# M129X.net
KiCad netlist of a schematic drawn in EAGLE
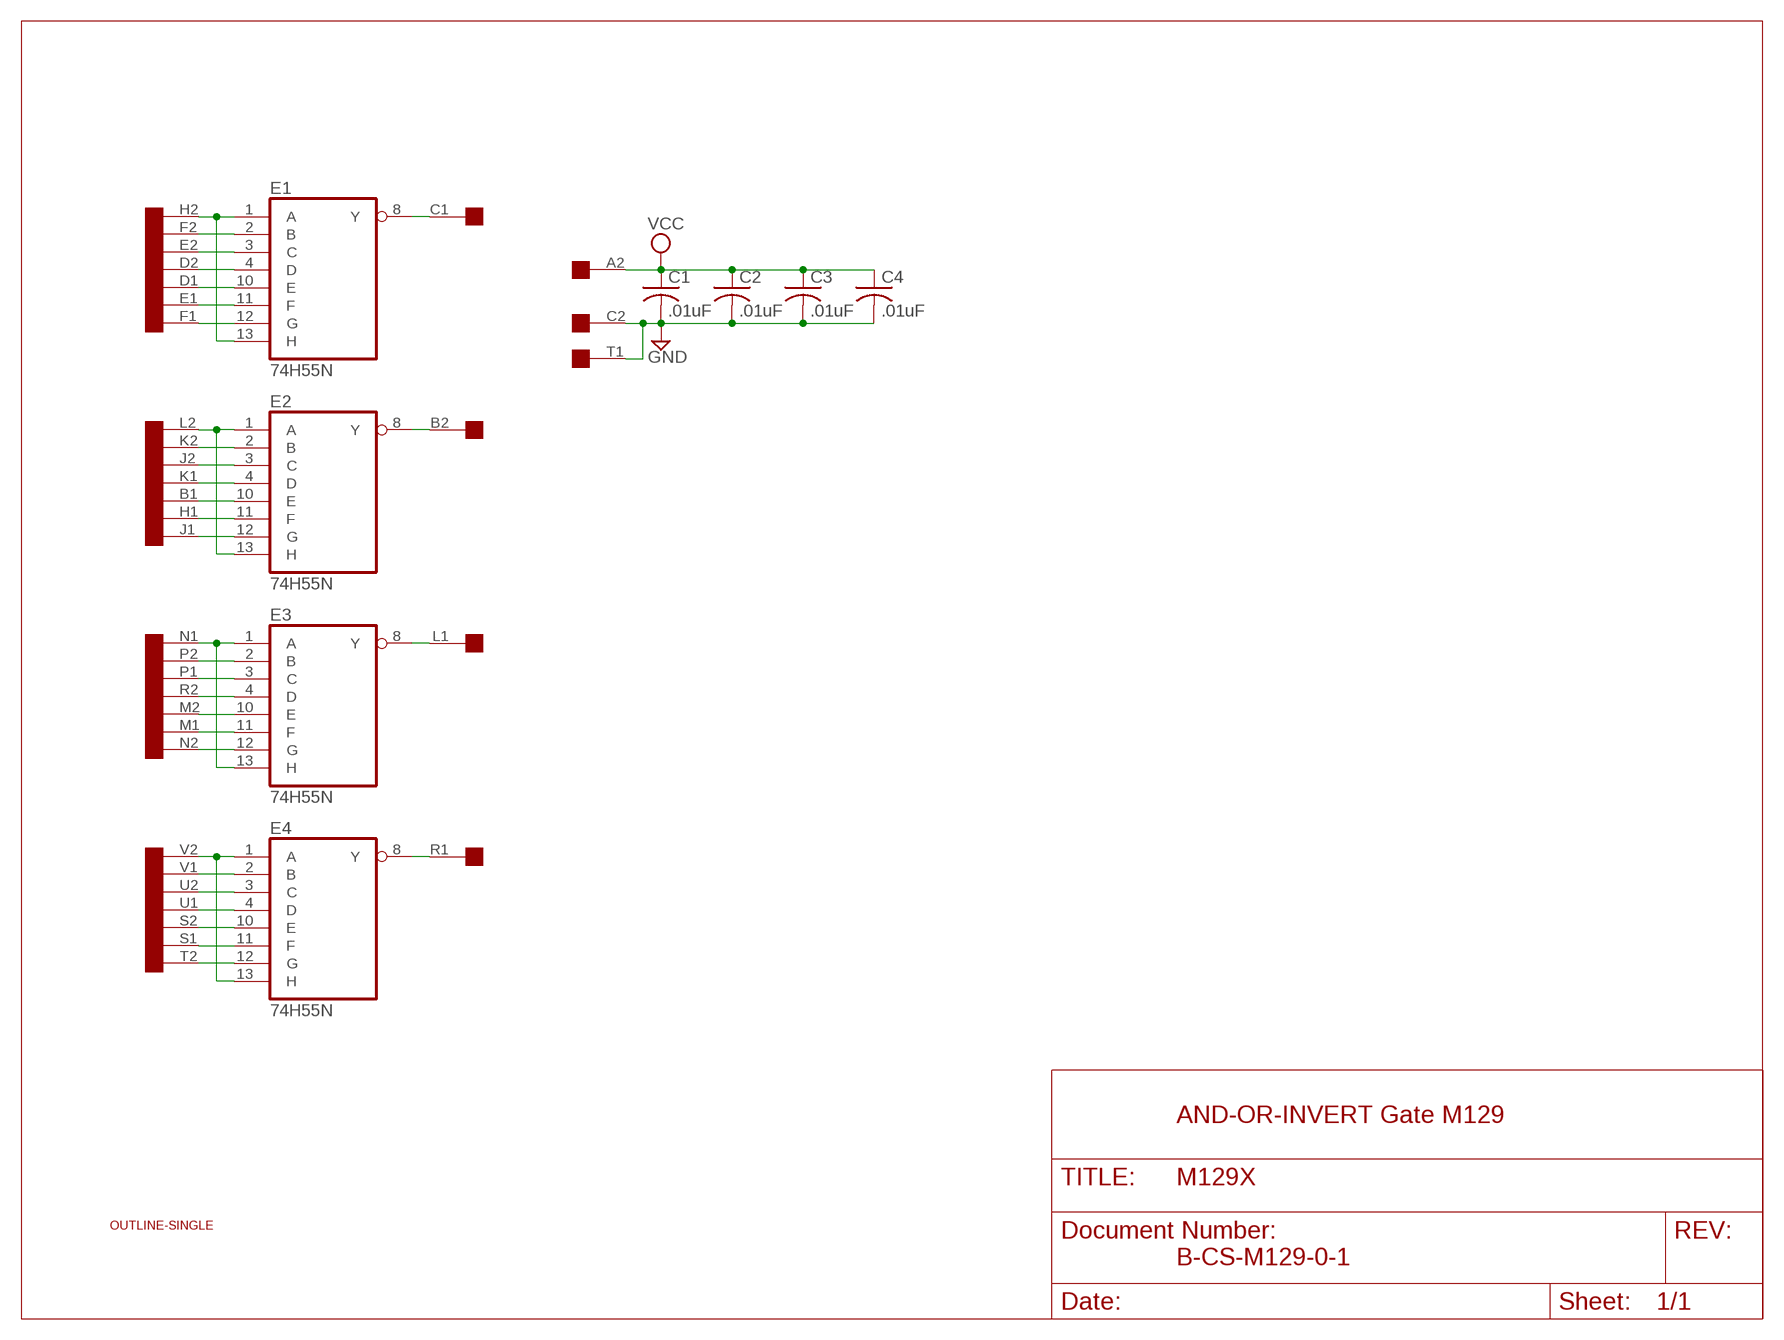
[diagram p0: schematic, sheet 1]

(export (version "E")
  (design (tool "Eeschema 10.0.6"))
  (components
    (comp (ref "C1")
      (value ".01uF")
      (footprint "eagle-import:C050-025X075")
      (libsource (lib "eagle-import") (part "C-US050-025X075"))
    )
    (comp (ref "C2")
      (value ".01uF")
      (footprint "eagle-import:C050-025X075")
      (libsource (lib "eagle-import") (part "C-US050-025X075"))
    )
    (comp (ref "C3")
      (value ".01uF")
      (footprint "eagle-import:C050-025X075")
      (libsource (lib "eagle-import") (part "C-US050-025X075"))
    )
    (comp (ref "C4")
      (value ".01uF")
      (footprint "eagle-import:C050-025X075")
      (libsource (lib "eagle-import") (part "C-US050-025X075"))
    )
    (comp (ref "E1")
      (value "74H55N")
      (footprint "eagle-import:DIL14")
      (libsource (lib "eagle-import") (part "7455NLS"))
    )
    (comp (ref "E2")
      (value "74H55N")
      (footprint "eagle-import:DIL14")
      (libsource (lib "eagle-import") (part "7455NLS"))
    )
    (comp (ref "E3")
      (value "74H55N")
      (footprint "eagle-import:DIL14")
      (libsource (lib "eagle-import") (part "7455NLS"))
    )
    (comp (ref "E4")
      (value "74H55N")
      (footprint "eagle-import:DIL14")
      (libsource (lib "eagle-import") (part "7455NLS"))
    )
    (comp (ref "U$1")
      (value "SINGLE")
      (footprint "eagle-import:EDGE-CON2")
      (libsource (lib "eagle-import") (part "SINGLE"))
    )
    (comp (ref "U$2")
      (value "OUTLINE-SINGLE")
      (footprint "eagle-import:SINGLE")
      (libsource (lib "eagle-import") (part "OUTLINE-SINGLE"))
    )
  )
  (nets
    (net (code "1") (name "GND") (class "Default")
      (node (ref "C1") (pin "2") (pinfunction "2_2") (pintype "passive"))
      (node (ref "C2") (pin "2") (pinfunction "2_2") (pintype "passive"))
      (node (ref "C3") (pin "2") (pinfunction "2_2") (pintype "passive"))
      (node (ref "C4") (pin "2") (pinfunction "2_2") (pintype "passive"))
      (node (ref "U$1") (pin "C2") (pinfunction "1_C2") (pintype "bidirectional"))
      (node (ref "U$1") (pin "T1") (pinfunction "1_T1") (pintype "bidirectional"))
    )
    (net (code "2") (name "Net-(E1A-A)") (class "Default")
      (node (ref "E1") (pin "1") (pinfunction "A_1") (pintype "input"))
      (node (ref "E1") (pin "13") (pinfunction "H_13") (pintype "input"))
      (node (ref "U$1") (pin "H2") (pinfunction "1_H2") (pintype "bidirectional"))
    )
    (net (code "3") (name "Net-(E1A-B)") (class "Default")
      (node (ref "E1") (pin "2") (pinfunction "B_2") (pintype "input"))
      (node (ref "U$1") (pin "F2") (pinfunction "1_F2") (pintype "bidirectional"))
    )
    (net (code "4") (name "Net-(E1A-C)") (class "Default")
      (node (ref "E1") (pin "3") (pinfunction "C_3") (pintype "input"))
      (node (ref "U$1") (pin "E2") (pinfunction "1_E2") (pintype "bidirectional"))
    )
    (net (code "5") (name "Net-(E1A-D)") (class "Default")
      (node (ref "E1") (pin "4") (pinfunction "D_4") (pintype "input"))
      (node (ref "U$1") (pin "D2") (pinfunction "1_D2") (pintype "bidirectional"))
    )
    (net (code "6") (name "Net-(E1A-E)") (class "Default")
      (node (ref "E1") (pin "10") (pinfunction "E_10") (pintype "input"))
      (node (ref "U$1") (pin "D1") (pinfunction "1_D1") (pintype "bidirectional"))
    )
    (net (code "7") (name "Net-(E1A-F)") (class "Default")
      (node (ref "E1") (pin "11") (pinfunction "F_11") (pintype "input"))
      (node (ref "U$1") (pin "E1") (pinfunction "1_E1") (pintype "bidirectional"))
    )
    (net (code "8") (name "Net-(E1A-G)") (class "Default")
      (node (ref "E1") (pin "12") (pinfunction "G_12") (pintype "input"))
      (node (ref "U$1") (pin "F1") (pinfunction "1_F1") (pintype "bidirectional"))
    )
    (net (code "9") (name "Net-(E1A-Y)") (class "Default")
      (node (ref "E1") (pin "8") (pinfunction "Y_8") (pintype "output"))
      (node (ref "U$1") (pin "C1") (pinfunction "1_C1") (pintype "bidirectional"))
    )
    (net (code "10") (name "Net-(E2A-A)") (class "Default")
      (node (ref "E2") (pin "1") (pinfunction "A_1") (pintype "input"))
      (node (ref "E2") (pin "13") (pinfunction "H_13") (pintype "input"))
      (node (ref "U$1") (pin "L2") (pinfunction "1_L2") (pintype "bidirectional"))
    )
    (net (code "11") (name "Net-(E2A-B)") (class "Default")
      (node (ref "E2") (pin "2") (pinfunction "B_2") (pintype "input"))
      (node (ref "U$1") (pin "K2") (pinfunction "1_K2") (pintype "bidirectional"))
    )
    (net (code "12") (name "Net-(E2A-C)") (class "Default")
      (node (ref "E2") (pin "3") (pinfunction "C_3") (pintype "input"))
      (node (ref "U$1") (pin "J2") (pinfunction "1_J2") (pintype "bidirectional"))
    )
    (net (code "13") (name "Net-(E2A-D)") (class "Default")
      (node (ref "E2") (pin "4") (pinfunction "D_4") (pintype "input"))
      (node (ref "U$1") (pin "K1") (pinfunction "1_K1") (pintype "bidirectional"))
    )
    (net (code "14") (name "Net-(E2A-E)") (class "Default")
      (node (ref "E2") (pin "10") (pinfunction "E_10") (pintype "input"))
      (node (ref "U$1") (pin "B1") (pinfunction "1_B1") (pintype "bidirectional"))
    )
    (net (code "15") (name "Net-(E2A-F)") (class "Default")
      (node (ref "E2") (pin "11") (pinfunction "F_11") (pintype "input"))
      (node (ref "U$1") (pin "H1") (pinfunction "1_H1") (pintype "bidirectional"))
    )
    (net (code "16") (name "Net-(E2A-G)") (class "Default")
      (node (ref "E2") (pin "12") (pinfunction "G_12") (pintype "input"))
      (node (ref "U$1") (pin "J1") (pinfunction "1_J1") (pintype "bidirectional"))
    )
    (net (code "17") (name "Net-(E2A-Y)") (class "Default")
      (node (ref "E2") (pin "8") (pinfunction "Y_8") (pintype "output"))
      (node (ref "U$1") (pin "B2") (pinfunction "1_B2") (pintype "bidirectional"))
    )
    (net (code "18") (name "Net-(E3A-A)") (class "Default")
      (node (ref "E3") (pin "1") (pinfunction "A_1") (pintype "input"))
      (node (ref "E3") (pin "13") (pinfunction "H_13") (pintype "input"))
      (node (ref "U$1") (pin "N1") (pinfunction "1_N1") (pintype "bidirectional"))
    )
    (net (code "19") (name "Net-(E3A-B)") (class "Default")
      (node (ref "E3") (pin "2") (pinfunction "B_2") (pintype "input"))
      (node (ref "U$1") (pin "P2") (pinfunction "1_P2") (pintype "bidirectional"))
    )
    (net (code "20") (name "Net-(E3A-C)") (class "Default")
      (node (ref "E3") (pin "3") (pinfunction "C_3") (pintype "input"))
      (node (ref "U$1") (pin "P1") (pinfunction "1_P1") (pintype "bidirectional"))
    )
    (net (code "21") (name "Net-(E3A-D)") (class "Default")
      (node (ref "E3") (pin "4") (pinfunction "D_4") (pintype "input"))
      (node (ref "U$1") (pin "R2") (pinfunction "1_R2") (pintype "bidirectional"))
    )
    (net (code "22") (name "Net-(E3A-E)") (class "Default")
      (node (ref "E3") (pin "10") (pinfunction "E_10") (pintype "input"))
      (node (ref "U$1") (pin "M2") (pinfunction "1_M2") (pintype "bidirectional"))
    )
    (net (code "23") (name "Net-(E3A-F)") (class "Default")
      (node (ref "E3") (pin "11") (pinfunction "F_11") (pintype "input"))
      (node (ref "U$1") (pin "M1") (pinfunction "1_M1") (pintype "bidirectional"))
    )
    (net (code "24") (name "Net-(E3A-G)") (class "Default")
      (node (ref "E3") (pin "12") (pinfunction "G_12") (pintype "input"))
      (node (ref "U$1") (pin "N2") (pinfunction "1_N2") (pintype "bidirectional"))
    )
    (net (code "25") (name "Net-(E3A-Y)") (class "Default")
      (node (ref "E3") (pin "8") (pinfunction "Y_8") (pintype "output"))
      (node (ref "U$1") (pin "L1") (pinfunction "1_L1") (pintype "bidirectional"))
    )
    (net (code "26") (name "Net-(E4A-A)") (class "Default")
      (node (ref "E4") (pin "1") (pinfunction "A_1") (pintype "input"))
      (node (ref "E4") (pin "13") (pinfunction "H_13") (pintype "input"))
      (node (ref "U$1") (pin "V2") (pinfunction "1_V2") (pintype "bidirectional"))
    )
    (net (code "27") (name "Net-(E4A-B)") (class "Default")
      (node (ref "E4") (pin "2") (pinfunction "B_2") (pintype "input"))
      (node (ref "U$1") (pin "V1") (pinfunction "1_V1") (pintype "bidirectional"))
    )
    (net (code "28") (name "Net-(E4A-C)") (class "Default")
      (node (ref "E4") (pin "3") (pinfunction "C_3") (pintype "input"))
      (node (ref "U$1") (pin "U2") (pinfunction "1_U2") (pintype "bidirectional"))
    )
    (net (code "29") (name "Net-(E4A-D)") (class "Default")
      (node (ref "E4") (pin "4") (pinfunction "D_4") (pintype "input"))
      (node (ref "U$1") (pin "U1") (pinfunction "1_U1") (pintype "bidirectional"))
    )
    (net (code "30") (name "Net-(E4A-E)") (class "Default")
      (node (ref "E4") (pin "10") (pinfunction "E_10") (pintype "input"))
      (node (ref "U$1") (pin "S2") (pinfunction "1_S2") (pintype "bidirectional"))
    )
    (net (code "31") (name "Net-(E4A-F)") (class "Default")
      (node (ref "E4") (pin "11") (pinfunction "F_11") (pintype "input"))
      (node (ref "U$1") (pin "S1") (pinfunction "1_S1") (pintype "bidirectional"))
    )
    (net (code "32") (name "Net-(E4A-G)") (class "Default")
      (node (ref "E4") (pin "12") (pinfunction "G_12") (pintype "input"))
      (node (ref "U$1") (pin "T2") (pinfunction "1_T2") (pintype "bidirectional"))
    )
    (net (code "33") (name "Net-(E4A-Y)") (class "Default")
      (node (ref "E4") (pin "8") (pinfunction "Y_8") (pintype "output"))
      (node (ref "U$1") (pin "R1") (pinfunction "1_R1") (pintype "bidirectional"))
    )
    (net (code "34") (name "VCC") (class "Default")
      (node (ref "C1") (pin "1") (pinfunction "1_1") (pintype "passive"))
      (node (ref "C2") (pin "1") (pinfunction "1_1") (pintype "passive"))
      (node (ref "C3") (pin "1") (pinfunction "1_1") (pintype "passive"))
      (node (ref "C4") (pin "1") (pinfunction "1_1") (pintype "passive"))
      (node (ref "U$1") (pin "A2") (pinfunction "1_A2") (pintype "bidirectional"))
    )
  )
)
